# POWERREG.net
KiCad netlist of a schematic drawn in Altium Designer
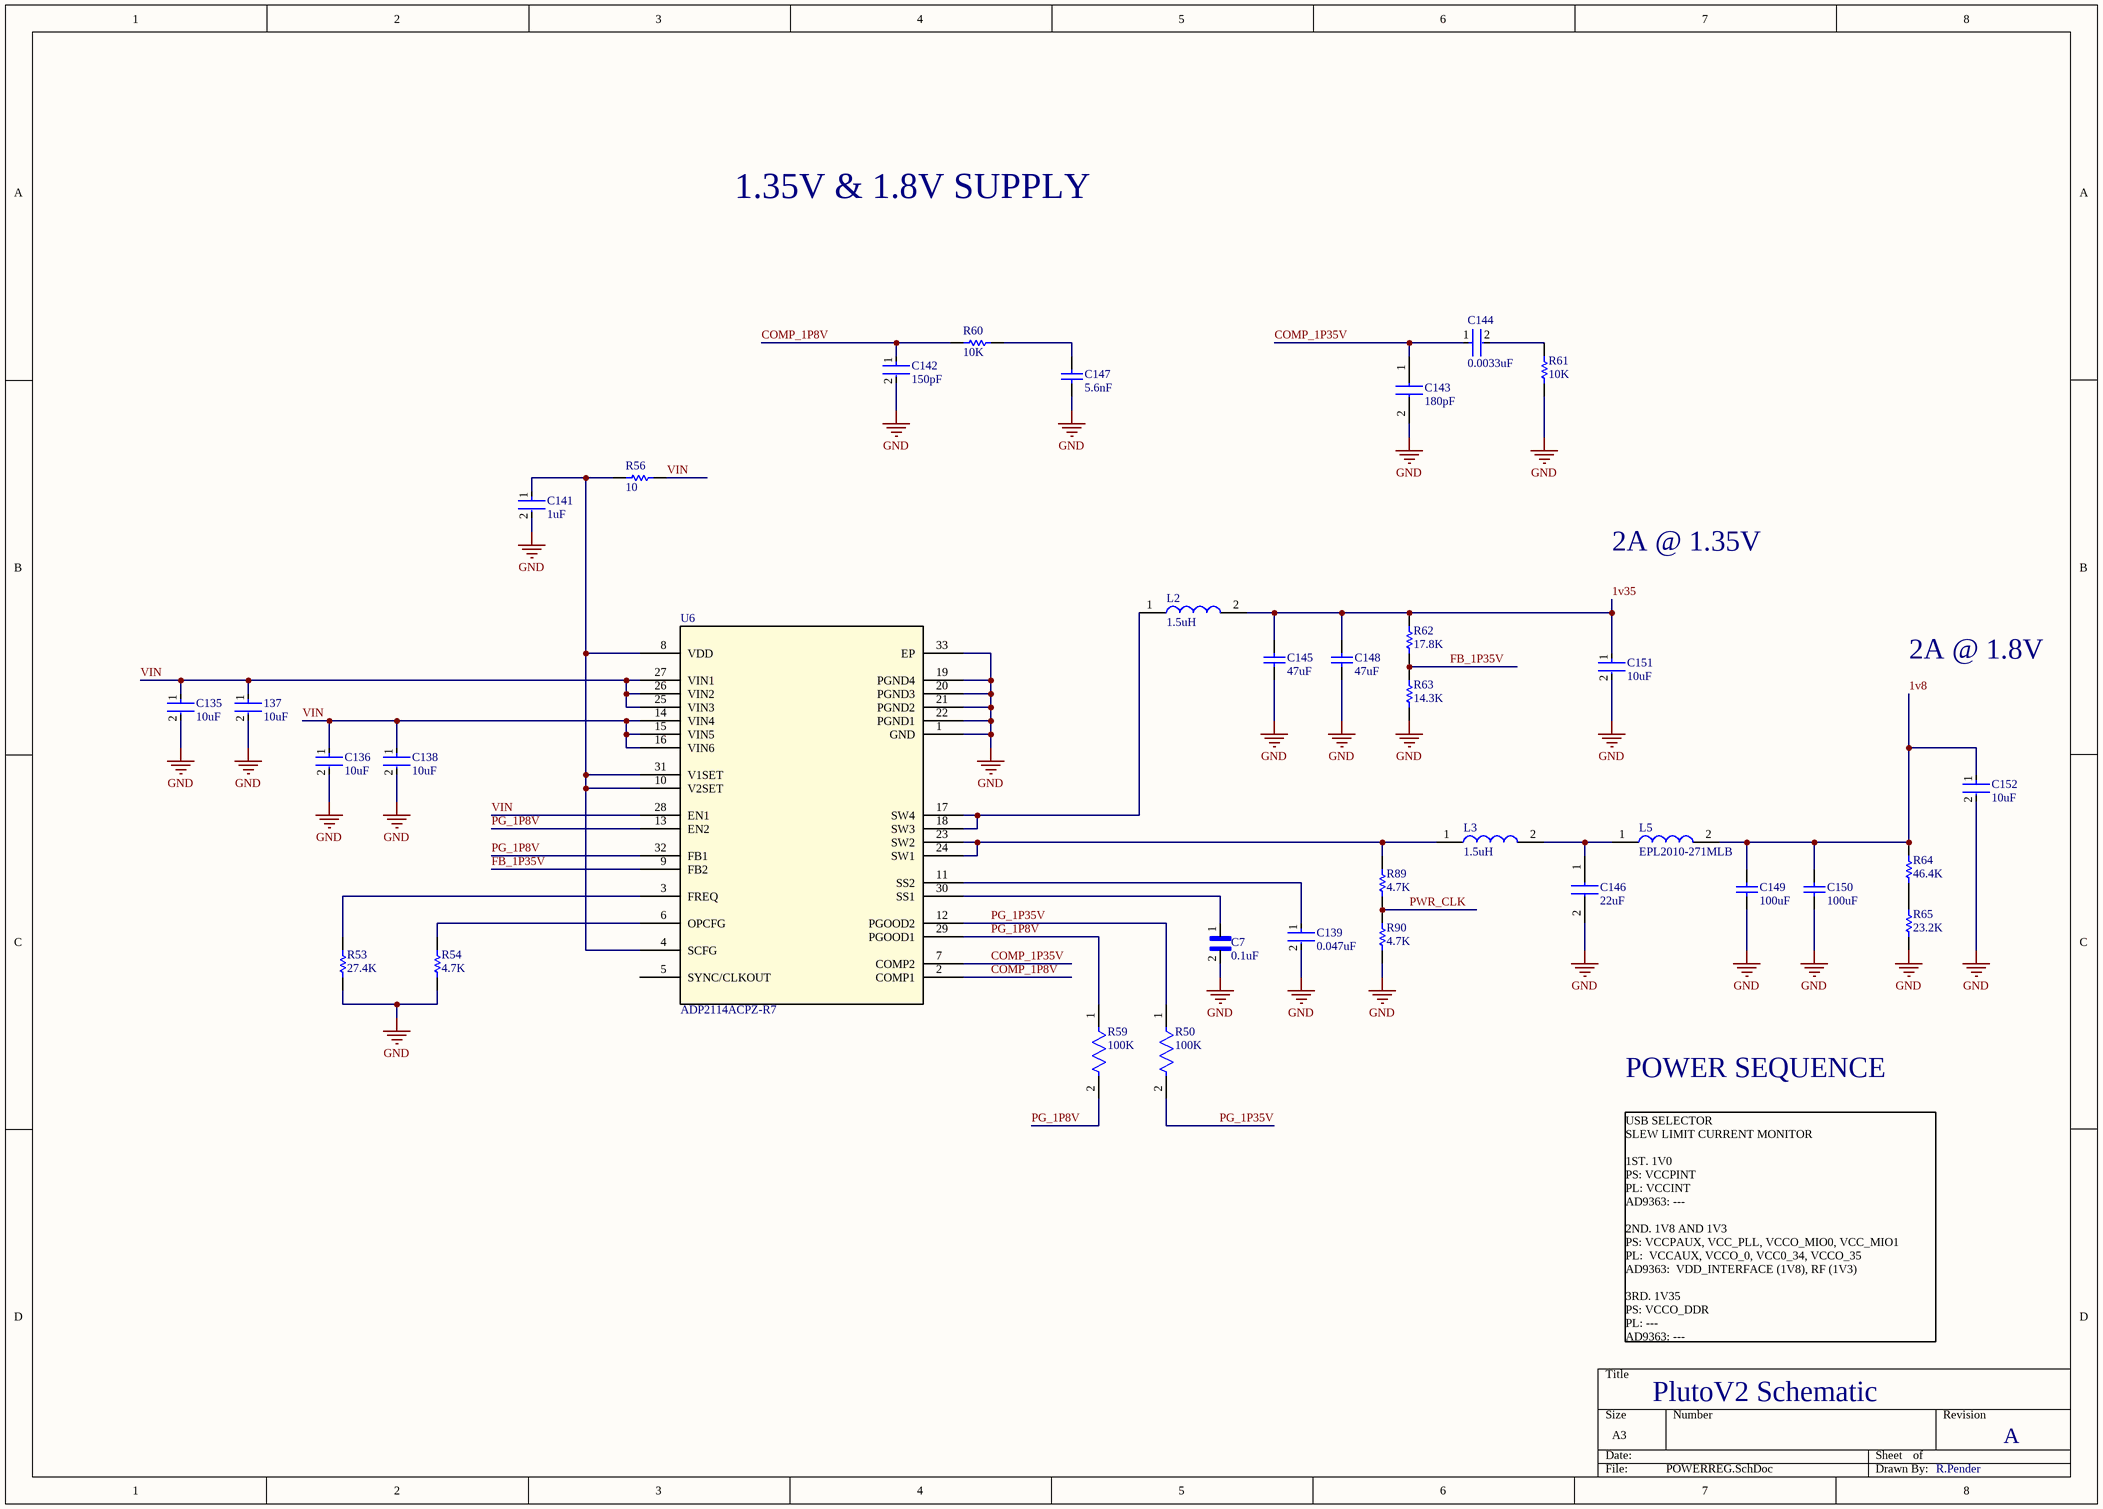
[diagram p0: POWERREG.SchDoc]

(export (version "E")
  (design (tool "Eeschema 10.0.6"))
  (components
    (comp (ref "137")
      (value "10uF")
      (footprint "FP-GRM188-0_15-MFG")
      (description "Chip Multilayer Ceramic Capacitors for General Purpose, 0603, 10uF, X5R, 15%, 20%, 10V")
      (fields (field (name "TOLERANCE") "20%"))
      (libsource (lib "Altium Content Vault") (part "02cd4be3c70576c341d710602a673aa"))
    )
    (comp (ref "C7")
      (value "0.1uF")
      (footprint "CAPC0603X33N")
      (description "CAP 0.1UF 16VDC X5R 20% SMD 0201 PAPER TAPE")
      (fields (field (name "MP") "GRM033R61C104ME84D"))
      (libsource (lib "GRM033R61C104ME84D") (part "GRM033R61C104ME84D"))
    )
    (comp (ref "C135")
      (value "10uF")
      (footprint "FP-GRM188-0_15-MFG")
      (description "Chip Multilayer Ceramic Capacitors for General Purpose, 0603, 10uF, X5R, 15%, 20%, 10V")
      (fields (field (name "TOLERANCE") "20%"))
      (libsource (lib "Altium Content Vault") (part "02cd4be3c70576c341d710602a673aa"))
    )
    (comp (ref "C136")
      (value "10uF")
      (footprint "FP-GRM188-0_15-MFG")
      (description "Chip Multilayer Ceramic Capacitors for General Purpose, 0603, 10uF, X5R, 15%, 20%, 10V")
      (fields (field (name "TOLERANCE") "20%"))
      (libsource (lib "Altium Content Vault") (part "02cd4be3c70576c341d710602a673aa"))
    )
    (comp (ref "C138")
      (value "10uF")
      (footprint "FP-GRM188-0_15-MFG")
      (description "Chip Multilayer Ceramic Capacitors for General Purpose, 0603, 10uF, X5R, 15%, 20%, 10V")
      (fields (field (name "TOLERANCE") "20%"))
      (libsource (lib "Altium Content Vault") (part "02cd4be3c70576c341d710602a673aa"))
    )
    (comp (ref "C139")
      (value "0.047uF")
      (footprint "FP-GCM155-0_05-IPC_C")
      (description "Ceramic Capacitor for Automotive 47nF ±10% 25VDC X7R 0402 Paper T/R")
      (fields (field (name "VOLTAGE") "25V") (field (name "TOLERANCE") "10%"))
      (libsource (lib "Altium Content Vault") (part "02cd4be3c70576c341d710602a673aa"))
    )
    (comp (ref "C141")
      (value "1uF")
      (footprint "FP-0402-L_1_0_0_05-W_0_5-IPC_A")
      (description "None")
      (fields (field (name "TOLERANCE") "10%"))
      (libsource (lib "Altium Content Vault") (part "b4654b650e69147ec39a6b967a45e02"))
    )
    (comp (ref "C142")
      (value "150pF")
      (footprint "FP-GCM155-0_05-IPC_C")
      (description "Ceramic Capacitor for Automotive 150pF ±1% 50VDC C0G 0402 Paper T/R")
      (libsource (lib "Altium Content Vault") (part "02cd4be3c70576c341d710602a673aa"))
    )
    (comp (ref "C143")
      (value "180pF")
      (footprint "SamacSys:CAPC1005X55N")
      (description "Capacitor")
      (fields (field (name "MANUFACTURER_PART_NUMBER") "CGJ2B2C0G1H181J050BA"))
      (libsource (lib "*") (part "CGJ2B2C0G1H181J050BA"))
    )
    (comp (ref "C144")
      (value "0.0033uF")
      (footprint "FP-CC0402-MFG")
      (description "CAP CER 3300PF 50V X7R 0402")
      (fields
        (field (name "OCTOPART") "https://octopart.com/cc0402krx7r9bb332-yageo-192887")
        (field (name "MANUFACTURER") "YAGEO")
      )
      (libsource (lib "Altium Content Vault") (part "11868f565c42a9108669ba33697ecf6"))
    )
    (comp (ref "C145")
      (value "47uF")
      (footprint "TAYO-JMK212BBJ476MG-T_L")
      (fields
        (field (name "MANUFACTURER") "Taiyo Yuden")
        (field (name "TOLERANCE") "±20%")
        (field (name "PCN PART NUMBER") "X5R,X7RDielectrics23/Jan/2008")
      )
      (libsource (lib "Altium Content Vault") (part "CAP-NP-2"))
    )
    (comp (ref "C146")
      (value "22uF")
      (footprint "SamacSys:CAPC2012X95N")
      (description "Capacitor")
      (fields (field (name "MANUFACTURER_PART_NUMBER") "CL21A226KPCLRNC"))
      (libsource (lib "*") (part "CL21A226KPCLRNC"))
    )
    (comp (ref "C147")
      (value "5.6nF")
      (footprint "CAPC1005X56X25NL10T15")
      (fields
        (field (name "MANUFACTURER") "AVX Interconnect / Elco")
        (field (name "PART NUMBER") "04025C562JAT2A")
      )
      (libsource (lib "Altium Content Vault") (part "CAP"))
    )
    (comp (ref "C148")
      (value "47uF")
      (footprint "TAYO-JMK212BBJ476MG-T_L")
      (fields
        (field (name "MANUFACTURER") "Taiyo Yuden")
        (field (name "TOLERANCE") "±20%")
        (field (name "PCN PART NUMBER") "X5R,X7RDielectrics23/Jan/2008")
      )
      (libsource (lib "Altium Content Vault") (part "CAP-NP-2"))
    )
    (comp (ref "C149")
      (value "100uF")
      (footprint "CAPC3216X190X55ML30T25")
      (description "Chip Capacitor, 100 uF, +/- 20%, 6.3 V, -55 to 85 degC, 1206 (3216 Metric), RoHS, Tape and Reel")
      (fields (field (name "TOLERANCE") "20%") (field (name "PARTNUMBER") "GRM31CR60J107ME39L"))
      (libsource (lib "Altium Content Vault") (part "CAP-NP-2"))
    )
    (comp (ref "C150")
      (value "100uF")
      (footprint "CAPC3216X190X55ML30T25")
      (description "Chip Capacitor, 100 uF, +/- 20%, 6.3 V, -55 to 85 degC, 1206 (3216 Metric), RoHS, Tape and Reel")
      (fields (field (name "TOLERANCE") "20%") (field (name "PARTNUMBER") "GRM31CR60J107ME39L"))
      (libsource (lib "Altium Content Vault") (part "CAP-NP-2"))
    )
    (comp (ref "C151")
      (value "10uF")
      (footprint "FP-GRM188-0_1-e0_2_0_55-IPC_A")
      (description "Chip Multilayer Ceramic Capacitors for General Purpose, 0603, 10uF, X5R, 15%, 20%, 6.3V")
      (fields (field (name "VOLTAGE") "6.3V") (field (name "TOLERANCE") "20%"))
      (libsource (lib "Altium Content Vault") (part "02cd4be3c70576c341d710602a673aa"))
    )
    (comp (ref "C152")
      (value "10uF")
      (footprint "FP-GRM188-0_1-e0_2_0_55-IPC_A")
      (description "Chip Multilayer Ceramic Capacitors for General Purpose, 0603, 10uF, X5R, 15%, 20%, 6.3V")
      (fields (field (name "VOLTAGE") "6.3V") (field (name "TOLERANCE") "20%"))
      (libsource (lib "Altium Content Vault") (part "02cd4be3c70576c341d710602a673aa"))
    )
    (comp (ref "L2")
      (value "1.5uH")
      (footprint "SamacSys:XFL4020152MEB")
      (description "Inductor")
      (fields
        (field (name "MOUSER2 PART NUMBER") "994-XFL4020-152MEB")
        (field (name "MANUFACTURER_PART_NUMBER") "XFL4020-152MEB")
      )
      (libsource (lib "*") (part "XFL4020-152MEB"))
    )
    (comp (ref "L3")
      (value "1.5uH")
      (footprint "SamacSys:XFL4020152MEB")
      (description "Inductor")
      (fields
        (field (name "MOUSER2 PART NUMBER") "994-XFL4020-152MEB")
        (field (name "MANUFACTURER_PART_NUMBER") "XFL4020-152MEB")
      )
      (libsource (lib "*") (part "XFL4020-152MEB"))
    )
    (comp (ref "L5")
      (value "EPL2010-271MLB")
      (footprint "SamacSys:EPL2010271MLB")
      (description "Inductor")
      (libsource (lib "*") (part "EPL2010-271MLB"))
    )
    (comp (ref "R50")
      (value "100K")
      (footprint "FP-ERJ2RK-IPC_C")
      (description "RES SMD 100K OHM 1% 1/10W 0402")
      (fields (field (name "TOLERANCE") "1%"))
      (libsource (lib "Altium Content Vault") (part "1029c3af85768c4190bb7ad29bc67b5"))
    )
    (comp (ref "R53")
      (value "27.4K")
      (footprint "2-0402")
      (fields (field (name "PUBLISHER") "Altium Limited"))
      (libsource (lib "Panasonic Resistor") (part "ERJ2RK"))
    )
    (comp (ref "R54")
      (value "4.7K")
      (footprint "2-0402")
      (fields (field (name "PUBLISHER") "Altium Limited"))
      (libsource (lib "Panasonic Resistor") (part "ERJ2RK"))
    )
    (comp (ref "R56")
      (value "10")
      (footprint "RESC0603X26X15LL03T05")
      (fields (field (name "MANUFACTURER") "Panasonic") (field (name "PART NUMBER") "ERJ1GNF10R0C"))
      (libsource (lib "Altium Content Vault") (part "RES"))
    )
    (comp (ref "R59")
      (value "100K")
      (footprint "FP-ERJ2RK-IPC_C")
      (description "RES SMD 100K OHM 1% 1/10W 0402")
      (fields (field (name "TOLERANCE") "1%"))
      (libsource (lib "Altium Content Vault") (part "1029c3af85768c4190bb7ad29bc67b5"))
    )
    (comp (ref "R60")
      (value "10K")
      (footprint "2-0402")
      (fields (field (name "PUBLISHER") "Altium Limited"))
      (libsource (lib "Panasonic Resistor") (part "ERJ2RK"))
    )
    (comp (ref "R61")
      (value "10K")
      (footprint "2-0402")
      (fields (field (name "PUBLISHER") "Altium Limited"))
      (libsource (lib "Panasonic Resistor") (part "ERJ2RK"))
    )
    (comp (ref "R62")
      (value "17.8K")
      (footprint "3-0603")
      (fields (field (name "PUBLISHER") "Altium Limited"))
      (libsource (lib "Panasonic Resistor") (part "ERJ3EK"))
    )
    (comp (ref "R63")
      (value "14.3K")
      (footprint "3-0603")
      (fields (field (name "PUBLISHER") "Altium Limited"))
      (libsource (lib "Panasonic Resistor") (part "ERJ3EK"))
    )
    (comp (ref "R64")
      (value "46.4K")
      (footprint "2-0402")
      (fields (field (name "PUBLISHER") "Altium Limited"))
      (libsource (lib "Panasonic Resistor") (part "ERJ2RK"))
    )
    (comp (ref "R65")
      (value "23.2K")
      (footprint "2-0402")
      (fields (field (name "PUBLISHER") "Altium Limited"))
      (libsource (lib "Panasonic Resistor") (part "ERJ2RK"))
    )
    (comp (ref "R89")
      (value "4.7K")
      (footprint "2-0402")
      (fields (field (name "PUBLISHER") "Altium Limited"))
      (libsource (lib "Panasonic Resistor") (part "ERJ2RK"))
    )
    (comp (ref "R90")
      (value "4.7K")
      (footprint "2-0402")
      (fields (field (name "PUBLISHER") "Altium Limited"))
      (libsource (lib "Panasonic Resistor") (part "ERJ2RK"))
    )
    (comp (ref "U6")
      (value "ADP2114ACPZ-R7")
      (footprint "CP_32_2_ADI")
      (description "No Description Available")
      (fields (field (name "COPYRIGHT") "Copyright (C) 2022 Ultra Librarian. All rights reserved."))
      (libsource (lib "ADP2114ACPZ-R7") (part "ADP2114ACPZ-R7"))
    )
  )
  (nets
    (net (code "1") (name "/1v8") (class "Default")
      (node (ref "C149") (pin "1") (pinfunction "1_1") (pintype "passive"))
      (node (ref "C150") (pin "1") (pinfunction "1_1") (pintype "passive"))
      (node (ref "C152") (pin "1") (pinfunction "1_1") (pintype "passive"))
      (node (ref "L5") (pin "2") (pinfunction "2_2") (pintype "passive"))
      (node (ref "R64") (pin "1") (pinfunction "1_1") (pintype "passive"))
    )
    (net (code "2") (name "/1v35") (class "Default")
      (node (ref "C145") (pin "1") (pinfunction "1_1") (pintype "passive"))
      (node (ref "C148") (pin "1") (pinfunction "1_1") (pintype "passive"))
      (node (ref "C151") (pin "1") (pinfunction "1_1") (pintype "passive"))
      (node (ref "L2") (pin "2") (pinfunction "2_2") (pintype "passive"))
      (node (ref "R62") (pin "1") (pinfunction "1_1") (pintype "passive"))
    )
    (net (code "3") (name "/COMP_1P8V") (class "Default")
      (node (ref "C142") (pin "1") (pinfunction "1_1") (pintype "passive"))
      (node (ref "R60") (pin "1") (pinfunction "1_1") (pintype "passive"))
      (node (ref "U6") (pin "2") (pinfunction "COMP1_2") (pintype "passive"))
    )
    (net (code "4") (name "/COMP_1P35V") (class "Default")
      (node (ref "C143") (pin "1") (pinfunction "1_1") (pintype "passive"))
      (node (ref "C144") (pin "1") (pinfunction "1_1") (pintype "passive"))
      (node (ref "U6") (pin "7") (pinfunction "COMP2_7") (pintype "passive"))
    )
    (net (code "5") (name "/FB_1P35V") (class "Default")
      (node (ref "R62") (pin "2") (pinfunction "2_2") (pintype "passive"))
      (node (ref "R63") (pin "1") (pinfunction "1_1") (pintype "passive"))
      (node (ref "U6") (pin "9") (pinfunction "FB2_9") (pintype "passive"))
    )
    (net (code "6") (name "/PG_1P8V") (class "Default")
      (node (ref "R59") (pin "1") (pinfunction "1_1") (pintype "passive"))
      (node (ref "R59") (pin "2") (pinfunction "2_2") (pintype "passive"))
      (node (ref "U6") (pin "13") (pinfunction "EN2_13") (pintype "passive"))
      (node (ref "U6") (pin "29") (pinfunction "PGOOD1_29") (pintype "passive"))
      (node (ref "U6") (pin "32") (pinfunction "FB1_32") (pintype "passive"))
    )
    (net (code "7") (name "/PG_1P35V") (class "Default")
      (node (ref "R50") (pin "1") (pinfunction "1_1") (pintype "passive"))
      (node (ref "R50") (pin "2") (pinfunction "2_2") (pintype "passive"))
      (node (ref "U6") (pin "12") (pinfunction "PGOOD2_12") (pintype "passive"))
    )
    (net (code "8") (name "/PWR_CLK") (class "Default")
      (node (ref "R89") (pin "2") (pinfunction "2_2") (pintype "passive"))
      (node (ref "R90") (pin "1") (pinfunction "1_1") (pintype "passive"))
    )
    (net (code "9") (name "/VIN") (class "Default")
      (node (ref "137") (pin "1") (pinfunction "1_1") (pintype "passive"))
      (node (ref "C135") (pin "1") (pinfunction "1_1") (pintype "passive"))
      (node (ref "C136") (pin "1") (pinfunction "1_1") (pintype "passive"))
      (node (ref "C138") (pin "1") (pinfunction "1_1") (pintype "passive"))
      (node (ref "R56") (pin "2") (pinfunction "2_2") (pintype "passive"))
      (node (ref "U6") (pin "14") (pinfunction "VIN4_14") (pintype "passive"))
      (node (ref "U6") (pin "15") (pinfunction "VIN5_15") (pintype "passive"))
      (node (ref "U6") (pin "16") (pinfunction "VIN6_16") (pintype "passive"))
      (node (ref "U6") (pin "25") (pinfunction "VIN3_25") (pintype "passive"))
      (node (ref "U6") (pin "26") (pinfunction "VIN2_26") (pintype "passive"))
      (node (ref "U6") (pin "27") (pinfunction "VIN1_27") (pintype "passive"))
      (node (ref "U6") (pin "28") (pinfunction "EN1_28") (pintype "passive"))
    )
    (net (code "10") (name "GND") (class "Default")
      (node (ref "137") (pin "2") (pinfunction "2_2") (pintype "passive"))
      (node (ref "C135") (pin "2") (pinfunction "2_2") (pintype "passive"))
      (node (ref "C136") (pin "2") (pinfunction "2_2") (pintype "passive"))
      (node (ref "C138") (pin "2") (pinfunction "2_2") (pintype "passive"))
      (node (ref "C139") (pin "2") (pinfunction "2_2") (pintype "passive"))
      (node (ref "C141") (pin "2") (pinfunction "2_2") (pintype "passive"))
      (node (ref "C142") (pin "2") (pinfunction "2_2") (pintype "passive"))
      (node (ref "C143") (pin "2") (pinfunction "2_2") (pintype "passive"))
      (node (ref "C145") (pin "2") (pinfunction "2_2") (pintype "passive"))
      (node (ref "C146") (pin "2") (pinfunction "2_2") (pintype "passive"))
      (node (ref "C147") (pin "2") (pinfunction "2_2") (pintype "passive"))
      (node (ref "C148") (pin "2") (pinfunction "2_2") (pintype "passive"))
      (node (ref "C149") (pin "2") (pinfunction "2_2") (pintype "passive"))
      (node (ref "C150") (pin "2") (pinfunction "2_2") (pintype "passive"))
      (node (ref "C151") (pin "2") (pinfunction "2_2") (pintype "passive"))
      (node (ref "C152") (pin "2") (pinfunction "2_2") (pintype "passive"))
      (node (ref "C7") (pin "2") (pinfunction "2_2") (pintype "passive"))
      (node (ref "R53") (pin "2") (pinfunction "2_2") (pintype "passive"))
      (node (ref "R54") (pin "2") (pinfunction "2_2") (pintype "passive"))
      (node (ref "R61") (pin "2") (pinfunction "2_2") (pintype "passive"))
      (node (ref "R63") (pin "2") (pinfunction "2_2") (pintype "passive"))
      (node (ref "R65") (pin "2") (pinfunction "2_2") (pintype "passive"))
      (node (ref "R90") (pin "2") (pinfunction "2_2") (pintype "passive"))
      (node (ref "U6") (pin "1") (pinfunction "GND_1") (pintype "passive"))
      (node (ref "U6") (pin "19") (pinfunction "PGND4_19") (pintype "passive"))
      (node (ref "U6") (pin "20") (pinfunction "PGND3_20") (pintype "passive"))
      (node (ref "U6") (pin "21") (pinfunction "PGND2_21") (pintype "passive"))
      (node (ref "U6") (pin "22") (pinfunction "PGND1_22") (pintype "passive"))
      (node (ref "U6") (pin "33") (pinfunction "EP_33") (pintype "passive"))
    )
    (net (code "11") (name "Net-(C144-Pad2)") (class "Default")
      (node (ref "C144") (pin "2") (pinfunction "2_2") (pintype "passive"))
      (node (ref "R61") (pin "1") (pinfunction "1_1") (pintype "passive"))
    )
    (net (code "12") (name "Net-(C146-Pad1)") (class "Default")
      (node (ref "C146") (pin "1") (pinfunction "1_1") (pintype "passive"))
      (node (ref "L3") (pin "2") (pinfunction "2_2") (pintype "passive"))
      (node (ref "L5") (pin "1") (pinfunction "1_1") (pintype "passive"))
    )
    (net (code "13") (name "Net-(C147-Pad1)") (class "Default")
      (node (ref "C147") (pin "1") (pinfunction "1_1") (pintype "passive"))
      (node (ref "R60") (pin "2") (pinfunction "2_2") (pintype "passive"))
    )
    (net (code "14") (name "Net-(R64-Pad2)") (class "Default")
      (node (ref "R64") (pin "2") (pinfunction "2_2") (pintype "passive"))
      (node (ref "R65") (pin "1") (pinfunction "1_1") (pintype "passive"))
    )
    (net (code "15") (name "Net-(U6-FREQ)") (class "Default")
      (node (ref "R53") (pin "1") (pinfunction "1_1") (pintype "passive"))
      (node (ref "U6") (pin "3") (pinfunction "FREQ_3") (pintype "passive"))
    )
    (net (code "16") (name "Net-(U6-OPCFG)") (class "Default")
      (node (ref "R54") (pin "1") (pinfunction "1_1") (pintype "passive"))
      (node (ref "U6") (pin "6") (pinfunction "OPCFG_6") (pintype "passive"))
    )
    (net (code "17") (name "Net-(U6-SCFG)") (class "Default")
      (node (ref "C141") (pin "1") (pinfunction "1_1") (pintype "passive"))
      (node (ref "R56") (pin "1") (pinfunction "1_1") (pintype "passive"))
      (node (ref "U6") (pin "10") (pinfunction "V2SET_10") (pintype "passive"))
      (node (ref "U6") (pin "31") (pinfunction "V1SET_31") (pintype "passive"))
      (node (ref "U6") (pin "4") (pinfunction "SCFG_4") (pintype "passive"))
      (node (ref "U6") (pin "8") (pinfunction "VDD_8") (pintype "passive"))
    )
    (net (code "18") (name "Net-(U6-SS1)") (class "Default")
      (node (ref "C7") (pin "1") (pinfunction "1_1") (pintype "passive"))
      (node (ref "U6") (pin "30") (pinfunction "SS1_30") (pintype "passive"))
    )
    (net (code "19") (name "Net-(U6-SS2)") (class "Default")
      (node (ref "C139") (pin "1") (pinfunction "1_1") (pintype "passive"))
      (node (ref "U6") (pin "11") (pinfunction "SS2_11") (pintype "passive"))
    )
    (net (code "20") (name "Net-(U6-SW1)") (class "Default")
      (node (ref "L3") (pin "1") (pinfunction "1_1") (pintype "passive"))
      (node (ref "R89") (pin "1") (pinfunction "1_1") (pintype "passive"))
      (node (ref "U6") (pin "23") (pinfunction "SW2_23") (pintype "passive"))
      (node (ref "U6") (pin "24") (pinfunction "SW1_24") (pintype "passive"))
    )
    (net (code "21") (name "Net-(U6-SW3)") (class "Default")
      (node (ref "L2") (pin "1") (pinfunction "1_1") (pintype "passive"))
      (node (ref "U6") (pin "17") (pinfunction "SW4_17") (pintype "passive"))
      (node (ref "U6") (pin "18") (pinfunction "SW3_18") (pintype "passive"))
    )
    (net (code "22") (name "unconnected-(U6-SYNC{slash}CLKOUT-Pad5)") (class "Default")
      (node (ref "U6") (pin "5") (pinfunction "SYNC/CLKOUT_5") (pintype "passive"))
    )
  )
)
